# RT-Weiche8.net
KiCad netlist of a schematic drawn in EAGLE
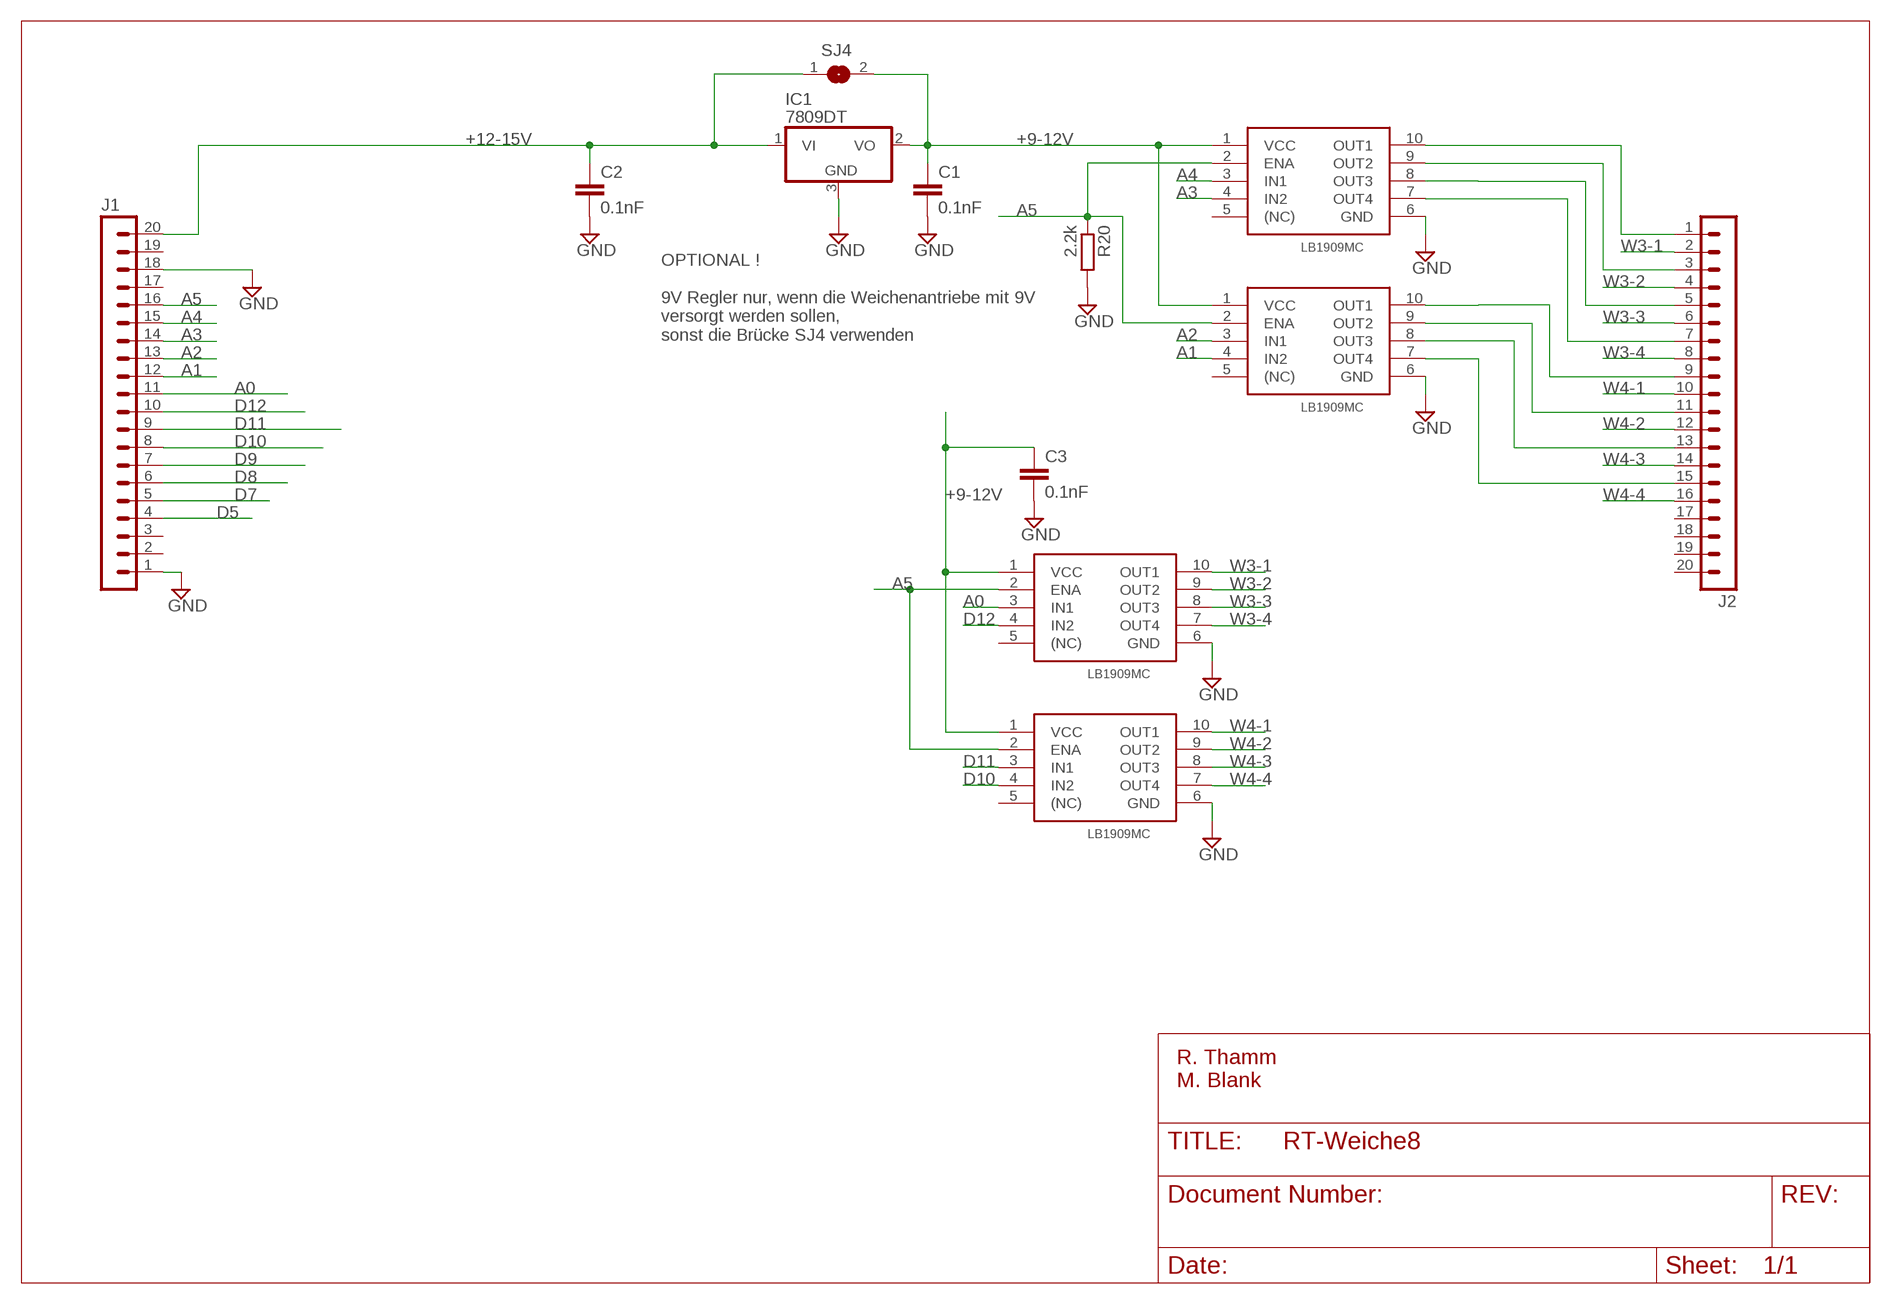
[diagram p0: schematic, sheet 1]

(export (version "E")
  (design (tool "Eeschema 10.0.6"))
  (components
    (comp (ref "C1")
      (value "0.1nF")
      (footprint "eagle-import:C0805K")
      (libsource (lib "eagle-import") (part "C-EUC0805K"))
    )
    (comp (ref "C2")
      (value "0.1nF")
      (footprint "eagle-import:C0805K")
      (libsource (lib "eagle-import") (part "C-EUC0805K"))
    )
    (comp (ref "C3")
      (value "0.1nF")
      (footprint "eagle-import:C0805K")
      (libsource (lib "eagle-import") (part "C-EUC0805K"))
    )
    (comp (ref "IC1")
      (value "7809DT")
      (footprint "eagle-import:TO252")
      (libsource (lib "eagle-import") (part "78DT05"))
    )
    (comp (ref "J1")
      (value "MA20-1")
      (footprint "eagle-import:MA20-1")
      (libsource (lib "eagle-import") (part "MA20-1"))
    )
    (comp (ref "J2")
      (value "MA20-1")
      (footprint "eagle-import:MA20-1")
      (libsource (lib "eagle-import") (part "MA20-1"))
    )
    (comp (ref "LB1909-1")
      (value "LB1909MC")
      (footprint "eagle-import:MSOIC10-1MM")
      (libsource (lib "eagle-import") (part "LB1909SOIC10"))
    )
    (comp (ref "LB1909-2")
      (value "LB1909MC")
      (footprint "eagle-import:MSOIC10-1MM")
      (libsource (lib "eagle-import") (part "LB1909SOIC10"))
    )
    (comp (ref "LB1909-3")
      (value "LB1909MC")
      (footprint "eagle-import:MSOIC10-1MM")
      (libsource (lib "eagle-import") (part "LB1909SOIC10"))
    )
    (comp (ref "LB1909-4")
      (value "LB1909MC")
      (footprint "eagle-import:MSOIC10-1MM")
      (libsource (lib "eagle-import") (part "LB1909SOIC10"))
    )
    (comp (ref "R20")
      (value "2.2k")
      (footprint "eagle-import:R0805W")
      (libsource (lib "eagle-import") (part "R-EU_R0805W"))
    )
    (comp (ref "SJ4") (value "SJ") (footprint "eagle-import:SJ") (libsource (lib "eagle-import") (part "SJ")))
  )
  (nets
    (net (code "1") (name "/+9-12V") (class "Default")
      (node (ref "C1") (pin "1") (pinfunction "1_1") (pintype "passive"))
      (node (ref "C3") (pin "1") (pinfunction "1_1") (pintype "passive"))
      (node (ref "IC1") (pin "2") (pinfunction "VO_2") (pintype "passive"))
      (node (ref "LB1909-1") (pin "1") (pinfunction "VCC_1") (pintype "power_in"))
      (node (ref "LB1909-2") (pin "1") (pinfunction "VCC_1") (pintype "power_in"))
      (node (ref "LB1909-3") (pin "1") (pinfunction "VCC_1") (pintype "power_in"))
      (node (ref "LB1909-4") (pin "1") (pinfunction "VCC_1") (pintype "power_in"))
      (node (ref "SJ4") (pin "2") (pinfunction "2_2") (pintype "passive"))
    )
    (net (code "2") (name "/+12-15V") (class "Default")
      (node (ref "C2") (pin "1") (pinfunction "1_1") (pintype "passive"))
      (node (ref "IC1") (pin "1") (pinfunction "VI_1") (pintype "input"))
      (node (ref "J1") (pin "20") (pinfunction "20_20") (pintype "passive"))
      (node (ref "SJ4") (pin "1") (pinfunction "1_1") (pintype "passive"))
    )
    (net (code "3") (name "/A0") (class "Default")
      (node (ref "J1") (pin "11") (pinfunction "11_11") (pintype "passive"))
      (node (ref "LB1909-3") (pin "3") (pinfunction "IN1_3") (pintype "input"))
    )
    (net (code "4") (name "/A1") (class "Default")
      (node (ref "J1") (pin "12") (pinfunction "12_12") (pintype "passive"))
      (node (ref "LB1909-2") (pin "4") (pinfunction "IN2_4") (pintype "input"))
    )
    (net (code "5") (name "/A2") (class "Default")
      (node (ref "J1") (pin "13") (pinfunction "13_13") (pintype "passive"))
      (node (ref "LB1909-2") (pin "3") (pinfunction "IN1_3") (pintype "input"))
    )
    (net (code "6") (name "/A3") (class "Default")
      (node (ref "J1") (pin "14") (pinfunction "14_14") (pintype "passive"))
      (node (ref "LB1909-1") (pin "4") (pinfunction "IN2_4") (pintype "input"))
    )
    (net (code "7") (name "/A4") (class "Default")
      (node (ref "J1") (pin "15") (pinfunction "15_15") (pintype "passive"))
      (node (ref "LB1909-1") (pin "3") (pinfunction "IN1_3") (pintype "input"))
    )
    (net (code "8") (name "/A5") (class "Default")
      (node (ref "J1") (pin "16") (pinfunction "16_16") (pintype "passive"))
      (node (ref "LB1909-1") (pin "2") (pinfunction "ENA_2") (pintype "input"))
      (node (ref "LB1909-2") (pin "2") (pinfunction "ENA_2") (pintype "input"))
      (node (ref "LB1909-3") (pin "2") (pinfunction "ENA_2") (pintype "input"))
      (node (ref "LB1909-4") (pin "2") (pinfunction "ENA_2") (pintype "input"))
      (node (ref "R20") (pin "1") (pinfunction "1_1") (pintype "passive"))
    )
    (net (code "9") (name "/D5") (class "Default")
      (node (ref "J1") (pin "4") (pinfunction "4_4") (pintype "passive"))
    )
    (net (code "10") (name "/D7") (class "Default")
      (node (ref "J1") (pin "5") (pinfunction "5_5") (pintype "passive"))
    )
    (net (code "11") (name "/D8") (class "Default")
      (node (ref "J1") (pin "6") (pinfunction "6_6") (pintype "passive"))
    )
    (net (code "12") (name "/D9") (class "Default")
      (node (ref "J1") (pin "7") (pinfunction "7_7") (pintype "passive"))
    )
    (net (code "13") (name "/D10") (class "Default")
      (node (ref "J1") (pin "8") (pinfunction "8_8") (pintype "passive"))
      (node (ref "LB1909-4") (pin "4") (pinfunction "IN2_4") (pintype "input"))
    )
    (net (code "14") (name "/D11") (class "Default")
      (node (ref "J1") (pin "9") (pinfunction "9_9") (pintype "passive"))
      (node (ref "LB1909-4") (pin "3") (pinfunction "IN1_3") (pintype "input"))
    )
    (net (code "15") (name "/D12") (class "Default")
      (node (ref "J1") (pin "10") (pinfunction "10_10") (pintype "passive"))
      (node (ref "LB1909-3") (pin "4") (pinfunction "IN2_4") (pintype "input"))
    )
    (net (code "16") (name "/W3-1") (class "Default")
      (node (ref "J2") (pin "2") (pinfunction "2_2") (pintype "passive"))
      (node (ref "LB1909-3") (pin "10") (pinfunction "OUT1_10") (pintype "output"))
    )
    (net (code "17") (name "/W3-2") (class "Default")
      (node (ref "J2") (pin "4") (pinfunction "4_4") (pintype "passive"))
      (node (ref "LB1909-3") (pin "9") (pinfunction "OUT2_9") (pintype "output"))
    )
    (net (code "18") (name "/W3-3") (class "Default")
      (node (ref "J2") (pin "6") (pinfunction "6_6") (pintype "passive"))
      (node (ref "LB1909-3") (pin "8") (pinfunction "OUT3_8") (pintype "output"))
    )
    (net (code "19") (name "/W3-4") (class "Default")
      (node (ref "J2") (pin "8") (pinfunction "8_8") (pintype "passive"))
      (node (ref "LB1909-3") (pin "7") (pinfunction "OUT4_7") (pintype "output"))
    )
    (net (code "20") (name "/W4-1") (class "Default")
      (node (ref "J2") (pin "10") (pinfunction "10_10") (pintype "passive"))
      (node (ref "LB1909-4") (pin "10") (pinfunction "OUT1_10") (pintype "output"))
    )
    (net (code "21") (name "/W4-2") (class "Default")
      (node (ref "J2") (pin "12") (pinfunction "12_12") (pintype "passive"))
      (node (ref "LB1909-4") (pin "9") (pinfunction "OUT2_9") (pintype "output"))
    )
    (net (code "22") (name "/W4-3") (class "Default")
      (node (ref "J2") (pin "14") (pinfunction "14_14") (pintype "passive"))
      (node (ref "LB1909-4") (pin "8") (pinfunction "OUT3_8") (pintype "output"))
    )
    (net (code "23") (name "/W4-4") (class "Default")
      (node (ref "J2") (pin "16") (pinfunction "16_16") (pintype "passive"))
      (node (ref "LB1909-4") (pin "7") (pinfunction "OUT4_7") (pintype "output"))
    )
    (net (code "24") (name "GND") (class "Default")
      (node (ref "C1") (pin "2") (pinfunction "2_2") (pintype "passive"))
      (node (ref "C2") (pin "2") (pinfunction "2_2") (pintype "passive"))
      (node (ref "C3") (pin "2") (pinfunction "2_2") (pintype "passive"))
      (node (ref "IC1") (pin "3") (pinfunction "GND_3") (pintype "passive"))
      (node (ref "J1") (pin "1") (pinfunction "1_1") (pintype "passive"))
      (node (ref "J1") (pin "18") (pinfunction "18_18") (pintype "passive"))
      (node (ref "LB1909-1") (pin "6") (pinfunction "GND_6") (pintype "power_in"))
      (node (ref "LB1909-2") (pin "6") (pinfunction "GND_6") (pintype "power_in"))
      (node (ref "LB1909-3") (pin "6") (pinfunction "GND_6") (pintype "power_in"))
      (node (ref "LB1909-4") (pin "6") (pinfunction "GND_6") (pintype "power_in"))
      (node (ref "R20") (pin "2") (pinfunction "2_2") (pintype "passive"))
    )
    (net (code "25") (name "Net-(LB1909-1-OUT1)") (class "Default")
      (node (ref "J2") (pin "1") (pinfunction "1_1") (pintype "passive"))
      (node (ref "LB1909-1") (pin "10") (pinfunction "OUT1_10") (pintype "output"))
    )
    (net (code "26") (name "Net-(LB1909-1-OUT2)") (class "Default")
      (node (ref "J2") (pin "3") (pinfunction "3_3") (pintype "passive"))
      (node (ref "LB1909-1") (pin "9") (pinfunction "OUT2_9") (pintype "output"))
    )
    (net (code "27") (name "Net-(LB1909-1-OUT3)") (class "Default")
      (node (ref "J2") (pin "5") (pinfunction "5_5") (pintype "passive"))
      (node (ref "LB1909-1") (pin "8") (pinfunction "OUT3_8") (pintype "output"))
    )
    (net (code "28") (name "Net-(LB1909-1-OUT4)") (class "Default")
      (node (ref "J2") (pin "7") (pinfunction "7_7") (pintype "passive"))
      (node (ref "LB1909-1") (pin "7") (pinfunction "OUT4_7") (pintype "output"))
    )
    (net (code "29") (name "Net-(LB1909-2-OUT1)") (class "Default")
      (node (ref "J2") (pin "9") (pinfunction "9_9") (pintype "passive"))
      (node (ref "LB1909-2") (pin "10") (pinfunction "OUT1_10") (pintype "output"))
    )
    (net (code "30") (name "Net-(LB1909-2-OUT2)") (class "Default")
      (node (ref "J2") (pin "11") (pinfunction "11_11") (pintype "passive"))
      (node (ref "LB1909-2") (pin "9") (pinfunction "OUT2_9") (pintype "output"))
    )
    (net (code "31") (name "Net-(LB1909-2-OUT3)") (class "Default")
      (node (ref "J2") (pin "13") (pinfunction "13_13") (pintype "passive"))
      (node (ref "LB1909-2") (pin "8") (pinfunction "OUT3_8") (pintype "output"))
    )
    (net (code "32") (name "Net-(LB1909-2-OUT4)") (class "Default")
      (node (ref "J2") (pin "15") (pinfunction "15_15") (pintype "passive"))
      (node (ref "LB1909-2") (pin "7") (pinfunction "OUT4_7") (pintype "output"))
    )
    (net (code "33") (name "unconnected-(J1-Pad2)") (class "Default")
      (node (ref "J1") (pin "2") (pinfunction "2_2") (pintype "passive"))
    )
    (net (code "34") (name "unconnected-(J1-Pad3)") (class "Default")
      (node (ref "J1") (pin "3") (pinfunction "3_3") (pintype "passive"))
    )
    (net (code "35") (name "unconnected-(J1-Pad17)") (class "Default")
      (node (ref "J1") (pin "17") (pinfunction "17_17") (pintype "passive"))
    )
    (net (code "36") (name "unconnected-(J1-Pad19)") (class "Default")
      (node (ref "J1") (pin "19") (pinfunction "19_19") (pintype "passive"))
    )
    (net (code "37") (name "unconnected-(J2-Pad17)") (class "Default")
      (node (ref "J2") (pin "17") (pinfunction "17_17") (pintype "passive"))
    )
    (net (code "38") (name "unconnected-(J2-Pad18)") (class "Default")
      (node (ref "J2") (pin "18") (pinfunction "18_18") (pintype "passive"))
    )
    (net (code "39") (name "unconnected-(J2-Pad19)") (class "Default")
      (node (ref "J2") (pin "19") (pinfunction "19_19") (pintype "passive"))
    )
    (net (code "40") (name "unconnected-(J2-Pad20)") (class "Default")
      (node (ref "J2") (pin "20") (pinfunction "20_20") (pintype "passive"))
    )
    (net (code "41") (name "unconnected-(LB1909-1-(NC)-Pad5)") (class "Default")
      (node (ref "LB1909-1") (pin "5") (pinfunction "(NC)_5") (pintype "no_connect"))
    )
    (net (code "42") (name "unconnected-(LB1909-2-(NC)-Pad5)") (class "Default")
      (node (ref "LB1909-2") (pin "5") (pinfunction "(NC)_5") (pintype "no_connect"))
    )
    (net (code "43") (name "unconnected-(LB1909-3-(NC)-Pad5)") (class "Default")
      (node (ref "LB1909-3") (pin "5") (pinfunction "(NC)_5") (pintype "no_connect"))
    )
    (net (code "44") (name "unconnected-(LB1909-4-(NC)-Pad5)") (class "Default")
      (node (ref "LB1909-4") (pin "5") (pinfunction "(NC)_5") (pintype "no_connect"))
    )
  )
)
